# Sensor_Board.net
KiCad netlist of a schematic drawn in EAGLE
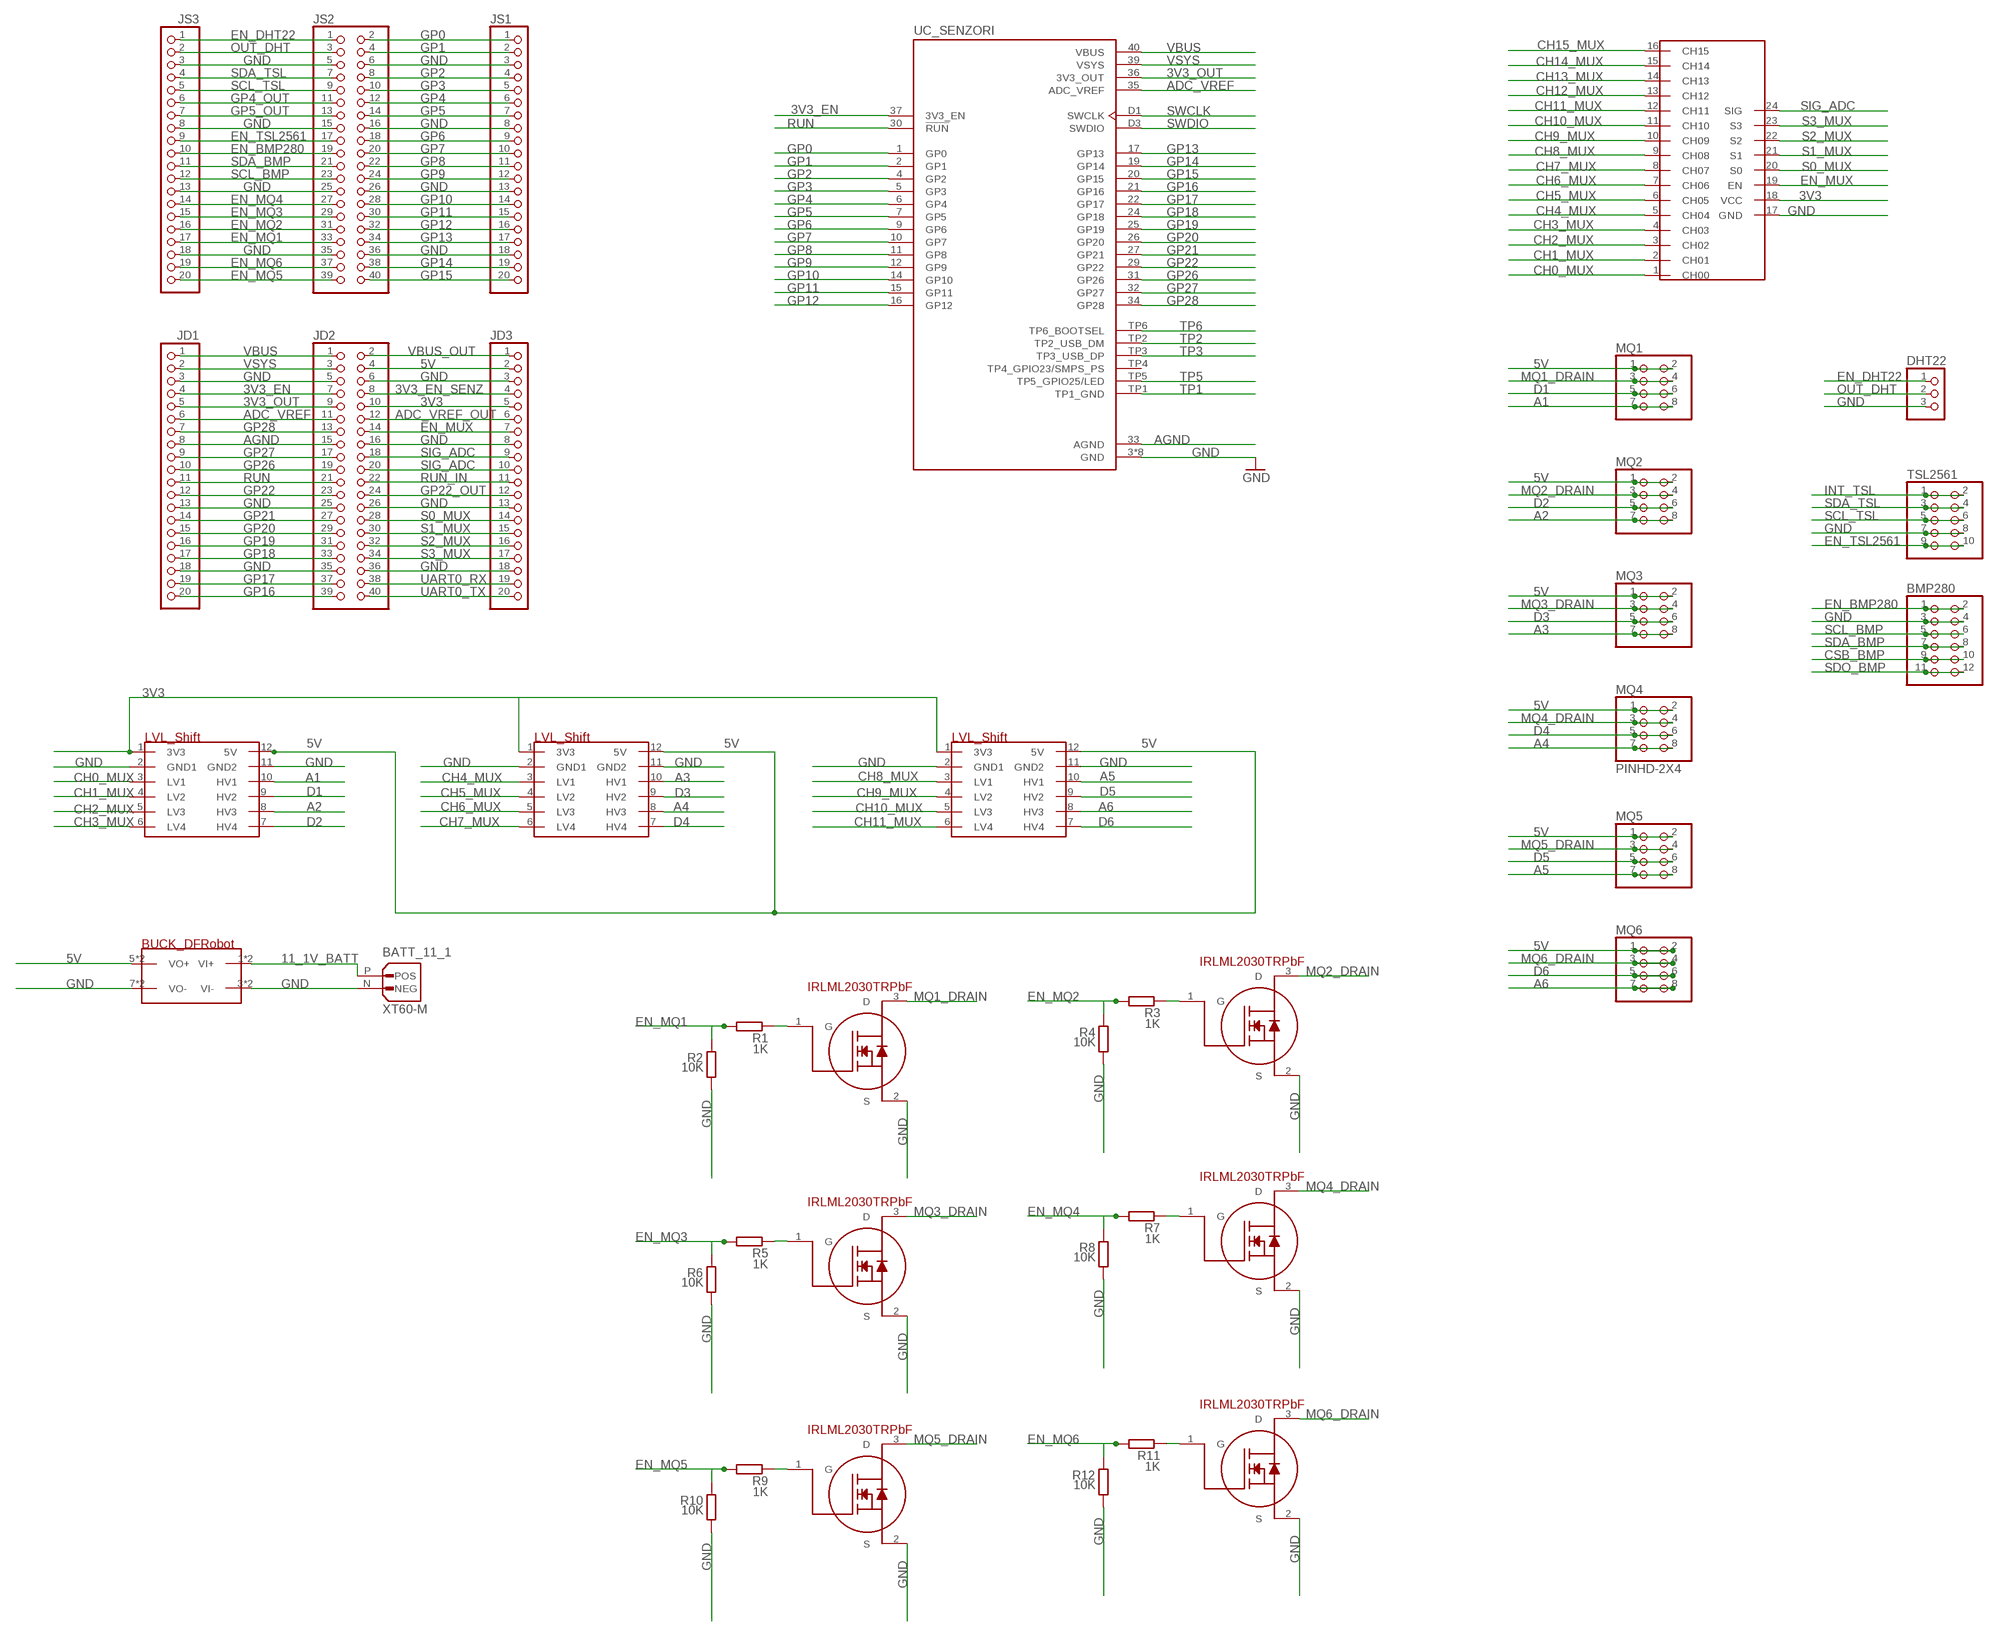
[diagram p0: schematic, sheet 1, part 1 of 2]
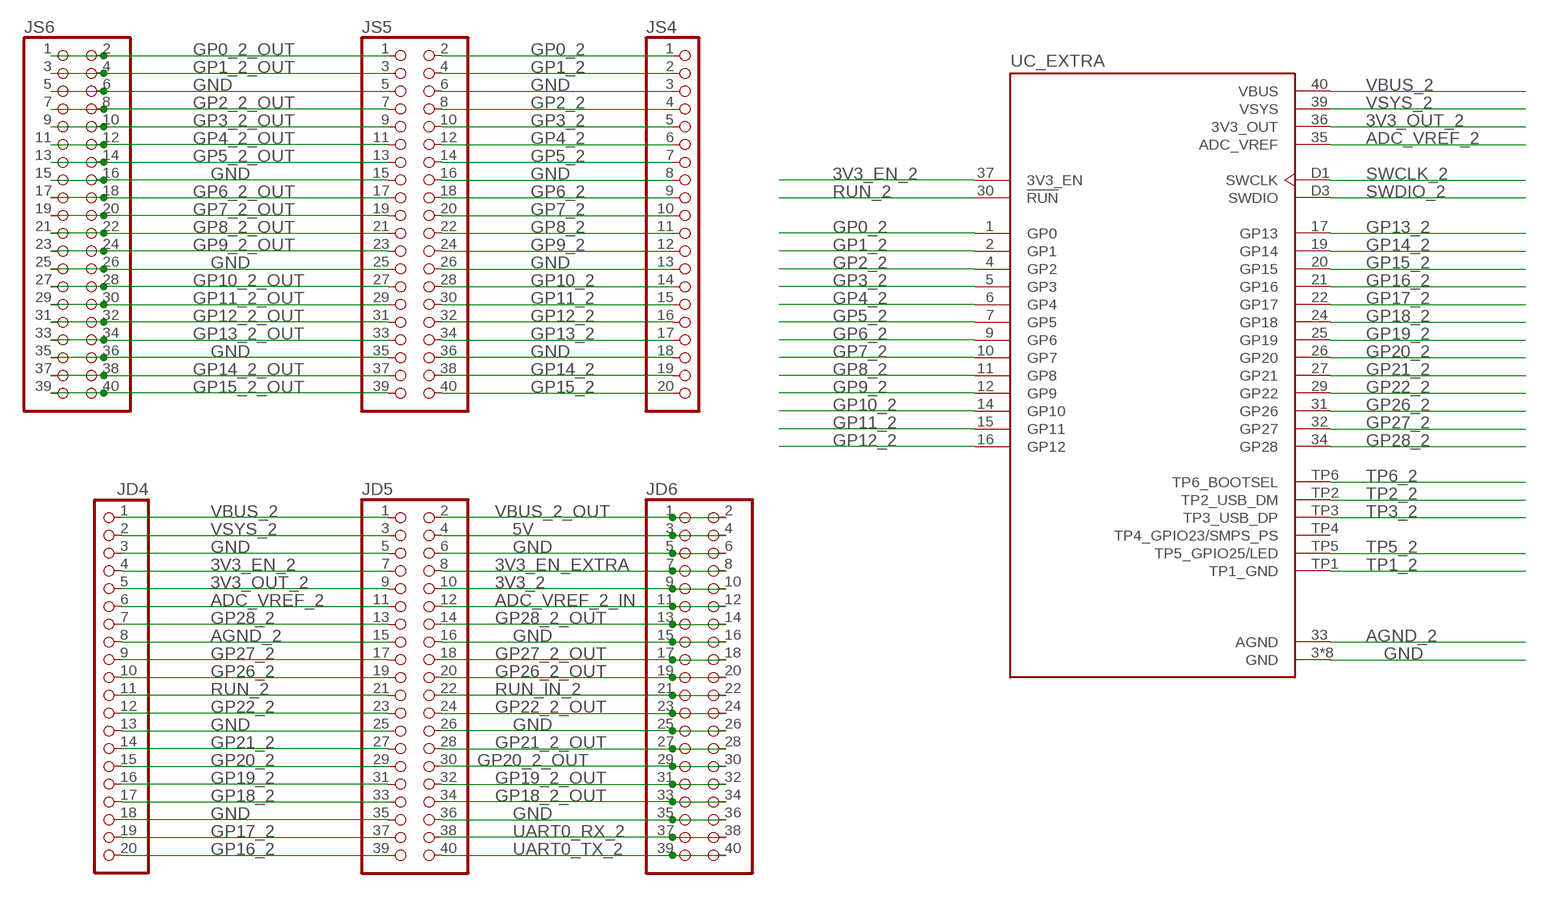
[diagram p1: schematic, sheet 1, part 2 of 2]

(export (version "E")
  (design (tool "Eeschema 10.0.6"))
  (components
    (comp (ref "BATT_11_1")
      (value "XT60-M")
      (footprint "eagle-import:AMASS_XT60-M")
      (fields (field (name "MANUFACTURER") "AMASS"))
      (libsource (lib "eagle-import") (part "XT60-M"))
    )
    (comp (ref "BMP280")
      (value "PINHD-2X6")
      (footprint "eagle-import:2X06")
      (libsource (lib "eagle-import") (part "PINHD-2X6"))
    )
    (comp (ref "DHT22")
      (value "PINHD-1X3")
      (footprint "eagle-import:1X03")
      (libsource (lib "eagle-import") (part "PINHD-1X3"))
    )
    (comp (ref "JD1")
      (value "PINHD-1X20")
      (footprint "eagle-import:1X20")
      (libsource (lib "eagle-import") (part "PINHD-1X20"))
    )
    (comp (ref "JD2")
      (value "PINHD-2X20")
      (footprint "eagle-import:2X20")
      (libsource (lib "eagle-import") (part "PINHD-2X20"))
    )
    (comp (ref "JD3")
      (value "PINHD-1X20")
      (footprint "eagle-import:1X20")
      (libsource (lib "eagle-import") (part "PINHD-1X20"))
    )
    (comp (ref "JD4")
      (value "PINHD-1X20")
      (footprint "eagle-import:1X20")
      (libsource (lib "eagle-import") (part "PINHD-1X20"))
    )
    (comp (ref "JD5")
      (value "PINHD-2X20")
      (footprint "eagle-import:2X20")
      (libsource (lib "eagle-import") (part "PINHD-2X20"))
    )
    (comp (ref "JD6")
      (value "PINHD-2X20")
      (footprint "eagle-import:2X20")
      (libsource (lib "eagle-import") (part "PINHD-2X20"))
    )
    (comp (ref "JS1")
      (value "PINHD-1X20")
      (footprint "eagle-import:1X20")
      (libsource (lib "eagle-import") (part "PINHD-1X20"))
    )
    (comp (ref "JS2")
      (value "PINHD-2X20")
      (footprint "eagle-import:2X20")
      (libsource (lib "eagle-import") (part "PINHD-2X20"))
    )
    (comp (ref "JS3")
      (value "PINHD-1X20")
      (footprint "eagle-import:1X20")
      (libsource (lib "eagle-import") (part "PINHD-1X20"))
    )
    (comp (ref "JS4")
      (value "PINHD-1X20")
      (footprint "eagle-import:1X20")
      (libsource (lib "eagle-import") (part "PINHD-1X20"))
    )
    (comp (ref "JS5")
      (value "PINHD-2X20")
      (footprint "eagle-import:2X20")
      (libsource (lib "eagle-import") (part "PINHD-2X20"))
    )
    (comp (ref "JS6")
      (value "PINHD-2X20")
      (footprint "eagle-import:2X20")
      (libsource (lib "eagle-import") (part "PINHD-2X20"))
    )
    (comp (ref "MQ1")
      (value "PINHD-2X4")
      (footprint "eagle-import:2X04")
      (libsource (lib "eagle-import") (part "PINHD-2X4"))
    )
    (comp (ref "MQ2")
      (value "PINHD-2X4")
      (footprint "eagle-import:2X04")
      (libsource (lib "eagle-import") (part "PINHD-2X4"))
    )
    (comp (ref "MQ3")
      (value "PINHD-2X4")
      (footprint "eagle-import:2X04")
      (libsource (lib "eagle-import") (part "PINHD-2X4"))
    )
    (comp (ref "MQ4")
      (value "PINHD-2X4")
      (footprint "eagle-import:2X04")
      (libsource (lib "eagle-import") (part "PINHD-2X4"))
    )
    (comp (ref "MQ5")
      (value "PINHD-2X4")
      (footprint "eagle-import:2X04")
      (libsource (lib "eagle-import") (part "PINHD-2X4"))
    )
    (comp (ref "MQ6")
      (value "PINHD-2X4")
      (footprint "eagle-import:2X04")
      (libsource (lib "eagle-import") (part "PINHD-2X4"))
    )
    (comp (ref "MUX")
      (value "CD74HC4067_MUX")
      (footprint "eagle-import:16_CH_MUX_FOOTPRINT")
      (libsource (lib "eagle-import") (part "CD74HC4067_MUX"))
    )
    (comp (ref "R1")
      (value "1K")
      (footprint "eagle-import:R0805")
      (libsource (lib "eagle-import") (part "R-EU_R0805"))
    )
    (comp (ref "R2")
      (value "10K")
      (footprint "eagle-import:R0805")
      (libsource (lib "eagle-import") (part "R-EU_R0805"))
    )
    (comp (ref "R3")
      (value "1K")
      (footprint "eagle-import:R0805")
      (libsource (lib "eagle-import") (part "R-EU_R0805"))
    )
    (comp (ref "R4")
      (value "10K")
      (footprint "eagle-import:R0805")
      (libsource (lib "eagle-import") (part "R-EU_R0805"))
    )
    (comp (ref "R5")
      (value "1K")
      (footprint "eagle-import:R0805")
      (libsource (lib "eagle-import") (part "R-EU_R0805"))
    )
    (comp (ref "R6")
      (value "10K")
      (footprint "eagle-import:R0805")
      (libsource (lib "eagle-import") (part "R-EU_R0805"))
    )
    (comp (ref "R7")
      (value "1K")
      (footprint "eagle-import:R0805")
      (libsource (lib "eagle-import") (part "R-EU_R0805"))
    )
    (comp (ref "R8")
      (value "10K")
      (footprint "eagle-import:R0805")
      (libsource (lib "eagle-import") (part "R-EU_R0805"))
    )
    (comp (ref "R9")
      (value "1K")
      (footprint "eagle-import:R0805")
      (libsource (lib "eagle-import") (part "R-EU_R0805"))
    )
    (comp (ref "R10")
      (value "10K")
      (footprint "eagle-import:R0805")
      (libsource (lib "eagle-import") (part "R-EU_R0805"))
    )
    (comp (ref "R11")
      (value "1K")
      (footprint "eagle-import:R0805")
      (libsource (lib "eagle-import") (part "R-EU_R0805"))
    )
    (comp (ref "R12")
      (value "10K")
      (footprint "eagle-import:R0805")
      (libsource (lib "eagle-import") (part "R-EU_R0805"))
    )
    (comp (ref "TSL2561")
      (value "PINHD-2X5")
      (footprint "eagle-import:2X05")
      (libsource (lib "eagle-import") (part "PINHD-2X5"))
    )
    (comp (ref "U$1")
      (value "IRLML2030TRBRBF_NMOS")
      (footprint "eagle-import:IRLML2030TRPBF_FOOTPRINT")
      (libsource (lib "eagle-import") (part "IRLML2030TRBRBF_NMOS"))
    )
    (comp (ref "U$2")
      (value "4_CH_BIDIRECTIONAL_LVL_SHIFTER")
      (footprint "eagle-import:LVL_SHIFT_FOOTPRINT")
      (libsource (lib "eagle-import") (part "4_CH_BIDIRECTIONAL_LVL_SHIFTER"))
    )
    (comp (ref "U$3")
      (value "4_CH_BIDIRECTIONAL_LVL_SHIFTER")
      (footprint "eagle-import:LVL_SHIFT_FOOTPRINT")
      (libsource (lib "eagle-import") (part "4_CH_BIDIRECTIONAL_LVL_SHIFTER"))
    )
    (comp (ref "U$4")
      (value "4_CH_BIDIRECTIONAL_LVL_SHIFTER")
      (footprint "eagle-import:LVL_SHIFT_FOOTPRINT")
      (libsource (lib "eagle-import") (part "4_CH_BIDIRECTIONAL_LVL_SHIFTER"))
    )
    (comp (ref "U$5")
      (value "DFROBOT_BUCK_CONVERTER")
      (footprint "eagle-import:DFROBOT_BUCK_FOOTPRINT")
      (libsource (lib "eagle-import") (part "DFROBOT_BUCK_CONVERTER"))
    )
    (comp (ref "U$7")
      (value "IRLML2030TRBRBF_NMOS")
      (footprint "eagle-import:IRLML2030TRPBF_FOOTPRINT")
      (libsource (lib "eagle-import") (part "IRLML2030TRBRBF_NMOS"))
    )
    (comp (ref "U$8")
      (value "IRLML2030TRBRBF_NMOS")
      (footprint "eagle-import:IRLML2030TRPBF_FOOTPRINT")
      (libsource (lib "eagle-import") (part "IRLML2030TRBRBF_NMOS"))
    )
    (comp (ref "U$9")
      (value "IRLML2030TRBRBF_NMOS")
      (footprint "eagle-import:IRLML2030TRPBF_FOOTPRINT")
      (libsource (lib "eagle-import") (part "IRLML2030TRBRBF_NMOS"))
    )
    (comp (ref "U$10")
      (value "IRLML2030TRBRBF_NMOS")
      (footprint "eagle-import:IRLML2030TRPBF_FOOTPRINT")
      (libsource (lib "eagle-import") (part "IRLML2030TRBRBF_NMOS"))
    )
    (comp (ref "U$11")
      (value "IRLML2030TRBRBF_NMOS")
      (footprint "eagle-import:IRLML2030TRPBF_FOOTPRINT")
      (libsource (lib "eagle-import") (part "IRLML2030TRBRBF_NMOS"))
    )
    (comp (ref "UC_EXTRA")
      (value "SC0915")
      (footprint "eagle-import:MODULE_SC0915")
      (fields (field (name "MF") "Raspberry Pi"))
      (libsource (lib "eagle-import") (part "SC0915"))
    )
    (comp (ref "UC_SENZORI")
      (value "SC0915")
      (footprint "eagle-import:MODULE_SC0915")
      (fields (field (name "MF") "Raspberry Pi"))
      (libsource (lib "eagle-import") (part "SC0915"))
    )
  )
  (nets
    (net (code "1") (name "/3V3") (class "Default")
      (node (ref "JD2") (pin "10") (pinfunction "10_10") (pintype "passive"))
      (node (ref "JD3") (pin "5") (pinfunction "5_5") (pintype "passive"))
      (node (ref "MUX") (pin "18") (pinfunction "VCC_18") (pintype "bidirectional"))
      (node (ref "U$2") (pin "1") (pinfunction "3V3_1") (pintype "bidirectional"))
      (node (ref "U$3") (pin "1") (pinfunction "3V3_1") (pintype "bidirectional"))
      (node (ref "U$4") (pin "1") (pinfunction "3V3_1") (pintype "bidirectional"))
    )
    (net (code "2") (name "/3V3_2") (class "Default")
      (node (ref "JD5") (pin "10") (pinfunction "10_10") (pintype "passive"))
      (node (ref "JD6") (pin "10") (pinfunction "10_10") (pintype "passive"))
      (node (ref "JD6") (pin "9") (pinfunction "9_9") (pintype "passive"))
    )
    (net (code "3") (name "/3V3_EN") (class "Default")
      (node (ref "JD1") (pin "4") (pinfunction "4_4") (pintype "passive"))
      (node (ref "JD2") (pin "7") (pinfunction "7_7") (pintype "passive"))
      (node (ref "UC_SENZORI") (pin "37") (pinfunction "3V3_EN_37") (pintype "input"))
    )
    (net (code "4") (name "/3V3_EN_2") (class "Default")
      (node (ref "JD4") (pin "4") (pinfunction "4_4") (pintype "passive"))
      (node (ref "JD5") (pin "7") (pinfunction "7_7") (pintype "passive"))
      (node (ref "UC_EXTRA") (pin "37") (pinfunction "3V3_EN_37") (pintype "input"))
    )
    (net (code "5") (name "/3V3_EN_EXTRA") (class "Default")
      (node (ref "JD5") (pin "8") (pinfunction "8_8") (pintype "passive"))
      (node (ref "JD6") (pin "7") (pinfunction "7_7") (pintype "passive"))
      (node (ref "JD6") (pin "8") (pinfunction "8_8") (pintype "passive"))
    )
    (net (code "6") (name "/3V3_EN_SENZ") (class "Default")
      (node (ref "JD2") (pin "8") (pinfunction "8_8") (pintype "passive"))
      (node (ref "JD3") (pin "4") (pinfunction "4_4") (pintype "passive"))
    )
    (net (code "7") (name "/3V3_OUT") (class "Default")
      (node (ref "JD1") (pin "5") (pinfunction "5_5") (pintype "passive"))
      (node (ref "JD2") (pin "9") (pinfunction "9_9") (pintype "passive"))
      (node (ref "UC_SENZORI") (pin "36") (pinfunction "3V3_OUT_36") (pintype "power_in"))
    )
    (net (code "8") (name "/3V3_OUT_2") (class "Default")
      (node (ref "JD4") (pin "5") (pinfunction "5_5") (pintype "passive"))
      (node (ref "JD5") (pin "9") (pinfunction "9_9") (pintype "passive"))
      (node (ref "UC_EXTRA") (pin "36") (pinfunction "3V3_OUT_36") (pintype "power_in"))
    )
    (net (code "9") (name "/5V") (class "Default")
      (node (ref "JD2") (pin "4") (pinfunction "4_4") (pintype "passive"))
      (node (ref "JD3") (pin "2") (pinfunction "2_2") (pintype "passive"))
      (node (ref "JD5") (pin "4") (pinfunction "4_4") (pintype "passive"))
      (node (ref "JD6") (pin "3") (pinfunction "3_3") (pintype "passive"))
      (node (ref "JD6") (pin "4") (pinfunction "4_4") (pintype "passive"))
      (node (ref "MQ1") (pin "1") (pinfunction "1_1") (pintype "passive"))
      (node (ref "MQ1") (pin "2") (pinfunction "2_2") (pintype "passive"))
      (node (ref "MQ2") (pin "1") (pinfunction "1_1") (pintype "passive"))
      (node (ref "MQ2") (pin "2") (pinfunction "2_2") (pintype "passive"))
      (node (ref "MQ3") (pin "1") (pinfunction "1_1") (pintype "passive"))
      (node (ref "MQ3") (pin "2") (pinfunction "2_2") (pintype "passive"))
      (node (ref "MQ4") (pin "1") (pinfunction "1_1") (pintype "passive"))
      (node (ref "MQ4") (pin "2") (pinfunction "2_2") (pintype "passive"))
      (node (ref "MQ5") (pin "1") (pinfunction "1_1") (pintype "passive"))
      (node (ref "MQ5") (pin "2") (pinfunction "2_2") (pintype "passive"))
      (node (ref "MQ6") (pin "1") (pinfunction "1_1") (pintype "passive"))
      (node (ref "MQ6") (pin "2") (pinfunction "2_2") (pintype "passive"))
      (node (ref "U$2") (pin "12") (pinfunction "5V_12") (pintype "bidirectional"))
      (node (ref "U$3") (pin "12") (pinfunction "5V_12") (pintype "bidirectional"))
      (node (ref "U$4") (pin "12") (pinfunction "5V_12") (pintype "bidirectional"))
      (node (ref "U$5") (pin "5") (pinfunction "VO+_5") (pintype "output"))
      (node (ref "U$5") (pin "6") (pinfunction "VO+_6") (pintype "output"))
    )
    (net (code "10") (name "/11_1V_BATT") (class "Default")
      (node (ref "BATT_11_1") (pin "P") (pinfunction "POS_P") (pintype "passive"))
      (node (ref "U$5") (pin "1") (pinfunction "VI+_1") (pintype "input"))
      (node (ref "U$5") (pin "2") (pinfunction "VI+_2") (pintype "input"))
    )
    (net (code "11") (name "/A1") (class "Default")
      (node (ref "MQ1") (pin "7") (pinfunction "7_7") (pintype "passive"))
      (node (ref "MQ1") (pin "8") (pinfunction "8_8") (pintype "passive"))
      (node (ref "U$2") (pin "10") (pinfunction "HV1_10") (pintype "bidirectional"))
    )
    (net (code "12") (name "/A2") (class "Default")
      (node (ref "MQ2") (pin "7") (pinfunction "7_7") (pintype "passive"))
      (node (ref "MQ2") (pin "8") (pinfunction "8_8") (pintype "passive"))
      (node (ref "U$2") (pin "8") (pinfunction "HV3_8") (pintype "bidirectional"))
    )
    (net (code "13") (name "/A3") (class "Default")
      (node (ref "MQ3") (pin "7") (pinfunction "7_7") (pintype "passive"))
      (node (ref "MQ3") (pin "8") (pinfunction "8_8") (pintype "passive"))
      (node (ref "U$3") (pin "10") (pinfunction "HV1_10") (pintype "bidirectional"))
    )
    (net (code "14") (name "/A4") (class "Default")
      (node (ref "MQ4") (pin "7") (pinfunction "7_7") (pintype "passive"))
      (node (ref "MQ4") (pin "8") (pinfunction "8_8") (pintype "passive"))
      (node (ref "U$3") (pin "8") (pinfunction "HV3_8") (pintype "bidirectional"))
    )
    (net (code "15") (name "/A5") (class "Default")
      (node (ref "MQ5") (pin "7") (pinfunction "7_7") (pintype "passive"))
      (node (ref "MQ5") (pin "8") (pinfunction "8_8") (pintype "passive"))
      (node (ref "U$4") (pin "10") (pinfunction "HV1_10") (pintype "bidirectional"))
    )
    (net (code "16") (name "/A6") (class "Default")
      (node (ref "MQ6") (pin "7") (pinfunction "7_7") (pintype "passive"))
      (node (ref "MQ6") (pin "8") (pinfunction "8_8") (pintype "passive"))
      (node (ref "U$4") (pin "8") (pinfunction "HV3_8") (pintype "bidirectional"))
    )
    (net (code "17") (name "/ADC_VREF") (class "Default")
      (node (ref "JD1") (pin "6") (pinfunction "6_6") (pintype "passive"))
      (node (ref "JD2") (pin "11") (pinfunction "11_11") (pintype "passive"))
      (node (ref "UC_SENZORI") (pin "35") (pinfunction "ADC_VREF_35") (pintype "power_in"))
    )
    (net (code "18") (name "/ADC_VREF_2") (class "Default")
      (node (ref "JD4") (pin "6") (pinfunction "6_6") (pintype "passive"))
      (node (ref "JD5") (pin "11") (pinfunction "11_11") (pintype "passive"))
      (node (ref "UC_EXTRA") (pin "35") (pinfunction "ADC_VREF_35") (pintype "power_in"))
    )
    (net (code "19") (name "/ADC_VREF_2_IN") (class "Default")
      (node (ref "JD5") (pin "12") (pinfunction "12_12") (pintype "passive"))
      (node (ref "JD6") (pin "11") (pinfunction "11_11") (pintype "passive"))
      (node (ref "JD6") (pin "12") (pinfunction "12_12") (pintype "passive"))
    )
    (net (code "20") (name "/ADC_VREF_OUT") (class "Default")
      (node (ref "JD2") (pin "12") (pinfunction "12_12") (pintype "passive"))
      (node (ref "JD3") (pin "6") (pinfunction "6_6") (pintype "passive"))
    )
    (net (code "21") (name "/AGND") (class "Default")
      (node (ref "JD1") (pin "8") (pinfunction "8_8") (pintype "passive"))
      (node (ref "JD2") (pin "15") (pinfunction "15_15") (pintype "passive"))
      (node (ref "UC_SENZORI") (pin "33") (pinfunction "AGND_33") (pintype "power_in"))
    )
    (net (code "22") (name "/AGND_2") (class "Default")
      (node (ref "JD4") (pin "8") (pinfunction "8_8") (pintype "passive"))
      (node (ref "JD5") (pin "15") (pinfunction "15_15") (pintype "passive"))
      (node (ref "UC_EXTRA") (pin "33") (pinfunction "AGND_33") (pintype "power_in"))
    )
    (net (code "23") (name "/CH0_MUX") (class "Default")
      (node (ref "MUX") (pin "1") (pinfunction "CH00_1") (pintype "bidirectional"))
      (node (ref "U$2") (pin "3") (pinfunction "LV1_3") (pintype "bidirectional"))
    )
    (net (code "24") (name "/CH1_MUX") (class "Default")
      (node (ref "MUX") (pin "2") (pinfunction "CH01_2") (pintype "bidirectional"))
      (node (ref "U$2") (pin "4") (pinfunction "LV2_4") (pintype "bidirectional"))
    )
    (net (code "25") (name "/CH2_MUX") (class "Default")
      (node (ref "MUX") (pin "3") (pinfunction "CH02_3") (pintype "bidirectional"))
      (node (ref "U$2") (pin "5") (pinfunction "LV3_5") (pintype "bidirectional"))
    )
    (net (code "26") (name "/CH3_MUX") (class "Default")
      (node (ref "MUX") (pin "4") (pinfunction "CH03_4") (pintype "bidirectional"))
      (node (ref "U$2") (pin "6") (pinfunction "LV4_6") (pintype "bidirectional"))
    )
    (net (code "27") (name "/CH4_MUX") (class "Default")
      (node (ref "MUX") (pin "5") (pinfunction "CH04_5") (pintype "bidirectional"))
      (node (ref "U$3") (pin "3") (pinfunction "LV1_3") (pintype "bidirectional"))
    )
    (net (code "28") (name "/CH5_MUX") (class "Default")
      (node (ref "MUX") (pin "6") (pinfunction "CH05_6") (pintype "bidirectional"))
      (node (ref "U$3") (pin "4") (pinfunction "LV2_4") (pintype "bidirectional"))
    )
    (net (code "29") (name "/CH6_MUX") (class "Default")
      (node (ref "MUX") (pin "7") (pinfunction "CH06_7") (pintype "bidirectional"))
      (node (ref "U$3") (pin "5") (pinfunction "LV3_5") (pintype "bidirectional"))
    )
    (net (code "30") (name "/CH7_MUX") (class "Default")
      (node (ref "MUX") (pin "8") (pinfunction "CH07_8") (pintype "bidirectional"))
      (node (ref "U$3") (pin "6") (pinfunction "LV4_6") (pintype "bidirectional"))
    )
    (net (code "31") (name "/CH8_MUX") (class "Default")
      (node (ref "MUX") (pin "9") (pinfunction "CH08_9") (pintype "bidirectional"))
      (node (ref "U$4") (pin "3") (pinfunction "LV1_3") (pintype "bidirectional"))
    )
    (net (code "32") (name "/CH9_MUX") (class "Default")
      (node (ref "MUX") (pin "10") (pinfunction "CH09_10") (pintype "bidirectional"))
      (node (ref "U$4") (pin "4") (pinfunction "LV2_4") (pintype "bidirectional"))
    )
    (net (code "33") (name "/CH10_MUX") (class "Default")
      (node (ref "MUX") (pin "11") (pinfunction "CH10_11") (pintype "bidirectional"))
      (node (ref "U$4") (pin "5") (pinfunction "LV3_5") (pintype "bidirectional"))
    )
    (net (code "34") (name "/CH11_MUX") (class "Default")
      (node (ref "MUX") (pin "12") (pinfunction "CH11_12") (pintype "bidirectional"))
      (node (ref "U$4") (pin "6") (pinfunction "LV4_6") (pintype "bidirectional"))
    )
    (net (code "35") (name "/CH12_MUX") (class "Default")
      (node (ref "MUX") (pin "13") (pinfunction "CH12_13") (pintype "bidirectional"))
    )
    (net (code "36") (name "/CH13_MUX") (class "Default")
      (node (ref "MUX") (pin "14") (pinfunction "CH13_14") (pintype "bidirectional"))
    )
    (net (code "37") (name "/CH14_MUX") (class "Default")
      (node (ref "MUX") (pin "15") (pinfunction "CH14_15") (pintype "bidirectional"))
    )
    (net (code "38") (name "/CH15_MUX") (class "Default")
      (node (ref "MUX") (pin "16") (pinfunction "CH15_16") (pintype "bidirectional"))
    )
    (net (code "39") (name "/CSB_BMP") (class "Default")
      (node (ref "BMP280") (pin "10") (pinfunction "10_10") (pintype "passive"))
      (node (ref "BMP280") (pin "9") (pinfunction "9_9") (pintype "passive"))
    )
    (net (code "40") (name "/D1") (class "Default")
      (node (ref "MQ1") (pin "5") (pinfunction "5_5") (pintype "passive"))
      (node (ref "MQ1") (pin "6") (pinfunction "6_6") (pintype "passive"))
      (node (ref "U$2") (pin "9") (pinfunction "HV2_9") (pintype "bidirectional"))
    )
    (net (code "41") (name "/D2") (class "Default")
      (node (ref "MQ2") (pin "5") (pinfunction "5_5") (pintype "passive"))
      (node (ref "MQ2") (pin "6") (pinfunction "6_6") (pintype "passive"))
      (node (ref "U$2") (pin "7") (pinfunction "HV4_7") (pintype "bidirectional"))
    )
    (net (code "42") (name "/D3") (class "Default")
      (node (ref "MQ3") (pin "5") (pinfunction "5_5") (pintype "passive"))
      (node (ref "MQ3") (pin "6") (pinfunction "6_6") (pintype "passive"))
      (node (ref "U$3") (pin "9") (pinfunction "HV2_9") (pintype "bidirectional"))
    )
    (net (code "43") (name "/D4") (class "Default")
      (node (ref "MQ4") (pin "5") (pinfunction "5_5") (pintype "passive"))
      (node (ref "MQ4") (pin "6") (pinfunction "6_6") (pintype "passive"))
      (node (ref "U$3") (pin "7") (pinfunction "HV4_7") (pintype "bidirectional"))
    )
    (net (code "44") (name "/D5") (class "Default")
      (node (ref "MQ5") (pin "5") (pinfunction "5_5") (pintype "passive"))
      (node (ref "MQ5") (pin "6") (pinfunction "6_6") (pintype "passive"))
      (node (ref "U$4") (pin "9") (pinfunction "HV2_9") (pintype "bidirectional"))
    )
    (net (code "45") (name "/D6") (class "Default")
      (node (ref "MQ6") (pin "5") (pinfunction "5_5") (pintype "passive"))
      (node (ref "MQ6") (pin "6") (pinfunction "6_6") (pintype "passive"))
      (node (ref "U$4") (pin "7") (pinfunction "HV4_7") (pintype "bidirectional"))
    )
    (net (code "46") (name "/EN_BMP280") (class "Default")
      (node (ref "BMP280") (pin "1") (pinfunction "1_1") (pintype "passive"))
      (node (ref "BMP280") (pin "2") (pinfunction "2_2") (pintype "passive"))
      (node (ref "JS2") (pin "19") (pinfunction "19_19") (pintype "passive"))
      (node (ref "JS3") (pin "10") (pinfunction "10_10") (pintype "passive"))
    )
    (net (code "47") (name "/EN_DHT22") (class "Default")
      (node (ref "DHT22") (pin "1") (pinfunction "1_1") (pintype "passive"))
      (node (ref "JS2") (pin "1") (pinfunction "1_1") (pintype "passive"))
      (node (ref "JS3") (pin "1") (pinfunction "1_1") (pintype "passive"))
    )
    (net (code "48") (name "/EN_MQ1") (class "Default")
      (node (ref "JS2") (pin "33") (pinfunction "33_33") (pintype "passive"))
      (node (ref "JS3") (pin "17") (pinfunction "17_17") (pintype "passive"))
      (node (ref "R1") (pin "2") (pinfunction "2_2") (pintype "passive"))
      (node (ref "R2") (pin "2") (pinfunction "2_2") (pintype "passive"))
    )
    (net (code "49") (name "/EN_MQ2") (class "Default")
      (node (ref "JS2") (pin "31") (pinfunction "31_31") (pintype "passive"))
      (node (ref "JS3") (pin "16") (pinfunction "16_16") (pintype "passive"))
      (node (ref "R3") (pin "2") (pinfunction "2_2") (pintype "passive"))
      (node (ref "R4") (pin "2") (pinfunction "2_2") (pintype "passive"))
    )
    (net (code "50") (name "/EN_MQ3") (class "Default")
      (node (ref "JS2") (pin "29") (pinfunction "29_29") (pintype "passive"))
      (node (ref "JS3") (pin "15") (pinfunction "15_15") (pintype "passive"))
      (node (ref "R5") (pin "2") (pinfunction "2_2") (pintype "passive"))
      (node (ref "R6") (pin "2") (pinfunction "2_2") (pintype "passive"))
    )
    (net (code "51") (name "/EN_MQ4") (class "Default")
      (node (ref "JS2") (pin "27") (pinfunction "27_27") (pintype "passive"))
      (node (ref "JS3") (pin "14") (pinfunction "14_14") (pintype "passive"))
      (node (ref "R7") (pin "2") (pinfunction "2_2") (pintype "passive"))
      (node (ref "R8") (pin "2") (pinfunction "2_2") (pintype "passive"))
    )
    (net (code "52") (name "/EN_MQ5") (class "Default")
      (node (ref "JS2") (pin "39") (pinfunction "39_39") (pintype "passive"))
      (node (ref "JS3") (pin "20") (pinfunction "20_20") (pintype "passive"))
      (node (ref "R10") (pin "2") (pinfunction "2_2") (pintype "passive"))
      (node (ref "R9") (pin "2") (pinfunction "2_2") (pintype "passive"))
    )
    (net (code "53") (name "/EN_MQ6") (class "Default")
      (node (ref "JS2") (pin "37") (pinfunction "37_37") (pintype "passive"))
      (node (ref "JS3") (pin "19") (pinfunction "19_19") (pintype "passive"))
      (node (ref "R11") (pin "2") (pinfunction "2_2") (pintype "passive"))
      (node (ref "R12") (pin "2") (pinfunction "2_2") (pintype "passive"))
    )
    (net (code "54") (name "/EN_MUX") (class "Default")
      (node (ref "JD2") (pin "14") (pinfunction "14_14") (pintype "passive"))
      (node (ref "JD3") (pin "7") (pinfunction "7_7") (pintype "passive"))
      (node (ref "MUX") (pin "19") (pinfunction "EN_19") (pintype "bidirectional"))
    )
    (net (code "55") (name "/EN_TSL2561") (class "Default")
      (node (ref "JS2") (pin "17") (pinfunction "17_17") (pintype "passive"))
      (node (ref "JS3") (pin "9") (pinfunction "9_9") (pintype "passive"))
      (node (ref "TSL2561") (pin "10") (pinfunction "10_10") (pintype "passive"))
      (node (ref "TSL2561") (pin "9") (pinfunction "9_9") (pintype "passive"))
    )
    (net (code "56") (name "/GP0") (class "Default")
      (node (ref "JS1") (pin "1") (pinfunction "1_1") (pintype "passive"))
      (node (ref "JS2") (pin "2") (pinfunction "2_2") (pintype "passive"))
      (node (ref "UC_SENZORI") (pin "1") (pinfunction "GP0_1") (pintype "bidirectional"))
    )
    (net (code "57") (name "/GP0_2") (class "Default")
      (node (ref "JS4") (pin "1") (pinfunction "1_1") (pintype "passive"))
      (node (ref "JS5") (pin "2") (pinfunction "2_2") (pintype "passive"))
      (node (ref "UC_EXTRA") (pin "1") (pinfunction "GP0_1") (pintype "bidirectional"))
    )
    (net (code "58") (name "/GP0_2_OUT") (class "Default")
      (node (ref "JS5") (pin "1") (pinfunction "1_1") (pintype "passive"))
      (node (ref "JS6") (pin "1") (pinfunction "1_1") (pintype "passive"))
      (node (ref "JS6") (pin "2") (pinfunction "2_2") (pintype "passive"))
    )
    (net (code "59") (name "/GP1") (class "Default")
      (node (ref "JS1") (pin "2") (pinfunction "2_2") (pintype "passive"))
      (node (ref "JS2") (pin "4") (pinfunction "4_4") (pintype "passive"))
      (node (ref "UC_SENZORI") (pin "2") (pinfunction "GP1_2") (pintype "bidirectional"))
    )
    (net (code "60") (name "/GP1_2") (class "Default")
      (node (ref "JS4") (pin "2") (pinfunction "2_2") (pintype "passive"))
      (node (ref "JS5") (pin "4") (pinfunction "4_4") (pintype "passive"))
      (node (ref "UC_EXTRA") (pin "2") (pinfunction "GP1_2") (pintype "bidirectional"))
    )
    (net (code "61") (name "/GP1_2_OUT") (class "Default")
      (node (ref "JS5") (pin "3") (pinfunction "3_3") (pintype "passive"))
      (node (ref "JS6") (pin "3") (pinfunction "3_3") (pintype "passive"))
      (node (ref "JS6") (pin "4") (pinfunction "4_4") (pintype "passive"))
    )
    (net (code "62") (name "/GP2") (class "Default")
      (node (ref "JS1") (pin "4") (pinfunction "4_4") (pintype "passive"))
      (node (ref "JS2") (pin "8") (pinfunction "8_8") (pintype "passive"))
      (node (ref "UC_SENZORI") (pin "4") (pinfunction "GP2_4") (pintype "bidirectional"))
    )
    (net (code "63") (name "/GP2_2") (class "Default")
      (node (ref "JS4") (pin "4") (pinfunction "4_4") (pintype "passive"))
      (node (ref "JS5") (pin "8") (pinfunction "8_8") (pintype "passive"))
      (node (ref "UC_EXTRA") (pin "4") (pinfunction "GP2_4") (pintype "bidirectional"))
    )
    (net (code "64") (name "/GP2_2_OUT") (class "Default")
      (node (ref "JS5") (pin "7") (pinfunction "7_7") (pintype "passive"))
      (node (ref "JS6") (pin "7") (pinfunction "7_7") (pintype "passive"))
      (node (ref "JS6") (pin "8") (pinfunction "8_8") (pintype "passive"))
    )
    (net (code "65") (name "/GP3") (class "Default")
      (node (ref "JS1") (pin "5") (pinfunction "5_5") (pintype "passive"))
      (node (ref "JS2") (pin "10") (pinfunction "10_10") (pintype "passive"))
      (node (ref "UC_SENZORI") (pin "5") (pinfunction "GP3_5") (pintype "bidirectional"))
    )
    (net (code "66") (name "/GP3_2") (class "Default")
      (node (ref "JS4") (pin "5") (pinfunction "5_5") (pintype "passive"))
      (node (ref "JS5") (pin "10") (pinfunction "10_10") (pintype "passive"))
      (node (ref "UC_EXTRA") (pin "5") (pinfunction "GP3_5") (pintype "bidirectional"))
    )
    (net (code "67") (name "/GP3_2_OUT") (class "Default")
      (node (ref "JS5") (pin "9") (pinfunction "9_9") (pintype "passive"))
      (node (ref "JS6") (pin "10") (pinfunction "10_10") (pintype "passive"))
      (node (ref "JS6") (pin "9") (pinfunction "9_9") (pintype "passive"))
    )
    (net (code "68") (name "/GP4") (class "Default")
      (node (ref "JS1") (pin "6") (pinfunction "6_6") (pintype "passive"))
      (node (ref "JS2") (pin "12") (pinfunction "12_12") (pintype "passive"))
      (node (ref "UC_SENZORI") (pin "6") (pinfunction "GP4_6") (pintype "bidirectional"))
    )
    (net (code "69") (name "/GP4_2") (class "Default")
      (node (ref "JS4") (pin "6") (pinfunction "6_6") (pintype "passive"))
      (node (ref "JS5") (pin "12") (pinfunction "12_12") (pintype "passive"))
      (node (ref "UC_EXTRA") (pin "6") (pinfunction "GP4_6") (pintype "bidirectional"))
    )
    (net (code "70") (name "/GP4_2_OUT") (class "Default")
      (node (ref "JS5") (pin "11") (pinfunction "11_11") (pintype "passive"))
      (node (ref "JS6") (pin "11") (pinfunction "11_11") (pintype "passive"))
      (node (ref "JS6") (pin "12") (pinfunction "12_12") (pintype "passive"))
    )
    (net (code "71") (name "/GP4_OUT") (class "Default")
      (node (ref "JS2") (pin "11") (pinfunction "11_11") (pintype "passive"))
      (node (ref "JS3") (pin "6") (pinfunction "6_6") (pintype "passive"))
    )
    (net (code "72") (name "/GP5") (class "Default")
      (node (ref "JS1") (pin "7") (pinfunction "7_7") (pintype "passive"))
      (node (ref "JS2") (pin "14") (pinfunction "14_14") (pintype "passive"))
      (node (ref "UC_SENZORI") (pin "7") (pinfunction "GP5_7") (pintype "bidirectional"))
    )
    (net (code "73") (name "/GP5_2") (class "Default")
      (node (ref "JS4") (pin "7") (pinfunction "7_7") (pintype "passive"))
      (node (ref "JS5") (pin "14") (pinfunction "14_14") (pintype "passive"))
      (node (ref "UC_EXTRA") (pin "7") (pinfunction "GP5_7") (pintype "bidirectional"))
    )
    (net (code "74") (name "/GP5_2_OUT") (class "Default")
      (node (ref "JS5") (pin "13") (pinfunction "13_13") (pintype "passive"))
      (node (ref "JS6") (pin "13") (pinfunction "13_13") (pintype "passive"))
      (node (ref "JS6") (pin "14") (pinfunction "14_14") (pintype "passive"))
    )
    (net (code "75") (name "/GP5_OUT") (class "Default")
      (node (ref "JS2") (pin "13") (pinfunction "13_13") (pintype "passive"))
      (node (ref "JS3") (pin "7") (pinfunction "7_7") (pintype "passive"))
    )
    (net (code "76") (name "/GP6") (class "Default")
      (node (ref "JS1") (pin "9") (pinfunction "9_9") (pintype "passive"))
      (node (ref "JS2") (pin "18") (pinfunction "18_18") (pintype "passive"))
      (node (ref "UC_SENZORI") (pin "9") (pinfunction "GP6_9") (pintype "bidirectional"))
    )
    (net (code "77") (name "/GP6_2") (class "Default")
      (node (ref "JS4") (pin "9") (pinfunction "9_9") (pintype "passive"))
      (node (ref "JS5") (pin "18") (pinfunction "18_18") (pintype "passive"))
      (node (ref "UC_EXTRA") (pin "9") (pinfunction "GP6_9") (pintype "bidirectional"))
    )
    (net (code "78") (name "/GP6_2_OUT") (class "Default")
      (node (ref "JS5") (pin "17") (pinfunction "17_17") (pintype "passive"))
      (node (ref "JS6") (pin "17") (pinfunction "17_17") (pintype "passive"))
      (node (ref "JS6") (pin "18") (pinfunction "18_18") (pintype "passive"))
    )
    (net (code "79") (name "/GP7") (class "Default")
      (node (ref "JS1") (pin "10") (pinfunction "10_10") (pintype "passive"))
      (node (ref "JS2") (pin "20") (pinfunction "20_20") (pintype "passive"))
      (node (ref "UC_SENZORI") (pin "10") (pinfunction "GP7_10") (pintype "bidirectional"))
    )
    (net (code "80") (name "/GP7_2") (class "Default")
      (node (ref "JS4") (pin "10") (pinfunction "10_10") (pintype "passive"))
      (node (ref "JS5") (pin "20") (pinfunction "20_20") (pintype "passive"))
      (node (ref "UC_EXTRA") (pin "10") (pinfunction "GP7_10") (pintype "bidirectional"))
    )
    (net (code "81") (name "/GP7_2_OUT") (class "Default")
      (node (ref "JS5") (pin "19") (pinfunction "19_19") (pintype "passive"))
      (node (ref "JS6") (pin "19") (pinfunction "19_19") (pintype "passive"))
      (node (ref "JS6") (pin "20") (pinfunction "20_20") (pintype "passive"))
    )
    (net (code "82") (name "/GP8") (class "Default")
      (node (ref "JS1") (pin "11") (pinfunction "11_11") (pintype "passive"))
      (node (ref "JS2") (pin "22") (pinfunction "22_22") (pintype "passive"))
      (node (ref "UC_SENZORI") (pin "11") (pinfunction "GP8_11") (pintype "bidirectional"))
    )
    (net (code "83") (name "/GP8_2") (class "Default")
      (node (ref "JS4") (pin "11") (pinfunction "11_11") (pintype "passive"))
      (node (ref "JS5") (pin "22") (pinfunction "22_22") (pintype "passive"))
      (node (ref "UC_EXTRA") (pin "11") (pinfunction "GP8_11") (pintype "bidirectional"))
    )
    (net (code "84") (name "/GP8_2_OUT") (class "Default")
      (node (ref "JS5") (pin "21") (pinfunction "21_21") (pintype "passive"))
      (node (ref "JS6") (pin "21") (pinfunction "21_21") (pintype "passive"))
      (node (ref "JS6") (pin "22") (pinfunction "22_22") (pintype "passive"))
    )
    (net (code "85") (name "/GP9") (class "Default")
      (node (ref "JS1") (pin "12") (pinfunction "12_12") (pintype "passive"))
      (node (ref "JS2") (pin "24") (pinfunction "24_24") (pintype "passive"))
      (node (ref "UC_SENZORI") (pin "12") (pinfunction "GP9_12") (pintype "bidirectional"))
    )
    (net (code "86") (name "/GP9_2") (class "Default")
      (node (ref "JS4") (pin "12") (pinfunction "12_12") (pintype "passive"))
      (node (ref "JS5") (pin "24") (pinfunction "24_24") (pintype "passive"))
      (node (ref "UC_EXTRA") (pin "12") (pinfunction "GP9_12") (pintype "bidirectional"))
    )
    (net (code "87") (name "/GP9_2_OUT") (class "Default")
      (node (ref "JS5") (pin "23") (pinfunction "23_23") (pintype "passive"))
      (node (ref "JS6") (pin "23") (pinfunction "23_23") (pintype "passive"))
      (node (ref "JS6") (pin "24") (pinfunction "24_24") (pintype "passive"))
    )
    (net (code "88") (name "/GP10") (class "Default")
      (node (ref "JS1") (pin "14") (pinfunction "14_14") (pintype "passive"))
      (node (ref "JS2") (pin "28") (pinfunction "28_28") (pintype "passive"))
      (node (ref "UC_SENZORI") (pin "14") (pinfunction "GP10_14") (pintype "bidirectional"))
    )
    (net (code "89") (name "/GP10_2") (class "Default")
      (node (ref "JS4") (pin "14") (pinfunction "14_14") (pintype "passive"))
      (node (ref "JS5") (pin "28") (pinfunction "28_28") (pintype "passive"))
      (node (ref "UC_EXTRA") (pin "14") (pinfunction "GP10_14") (pintype "bidirectional"))
    )
    (net (code "90") (name "/GP10_2_OUT") (class "Default")
      (node (ref "JS5") (pin "27") (pinfunction "27_27") (pintype "passive"))
      (node (ref "JS6") (pin "27") (pinfunction "27_27") (pintype "passive"))
      (node (ref "JS6") (pin "28") (pinfunction "28_28") (pintype "passive"))
    )
    (net (code "91") (name "/GP11") (class "Default")
      (node (ref "JS1") (pin "15") (pinfunction "15_15") (pintype "passive"))
      (node (ref "JS2") (pin "30") (pinfunction "30_30") (pintype "passive"))
      (node (ref "UC_SENZORI") (pin "15") (pinfunction "GP11_15") (pintype "bidirectional"))
    )
    (net (code "92") (name "/GP11_2") (class "Default")
      (node (ref "JS4") (pin "15") (pinfunction "15_15") (pintype "passive"))
      (node (ref "JS5") (pin "30") (pinfunction "30_30") (pintype "passive"))
      (node (ref "UC_EXTRA") (pin "15") (pinfunction "GP11_15") (pintype "bidirectional"))
    )
    (net (code "93") (name "/GP11_2_OUT") (class "Default")
      (node (ref "JS5") (pin "29") (pinfunction "29_29") (pintype "passive"))
      (node (ref "JS6") (pin "29") (pinfunction "29_29") (pintype "passive"))
      (node (ref "JS6") (pin "30") (pinfunction "30_30") (pintype "passive"))
    )
    (net (code "94") (name "/GP12") (class "Default")
      (node (ref "JS1") (pin "16") (pinfunction "16_16") (pintype "passive"))
      (node (ref "JS2") (pin "32") (pinfunction "32_32") (pintype "passive"))
      (node (ref "UC_SENZORI") (pin "16") (pinfunction "GP12_16") (pintype "bidirectional"))
    )
    (net (code "95") (name "/GP12_2") (class "Default")
      (node (ref "JS4") (pin "16") (pinfunction "16_16") (pintype "passive"))
      (node (ref "JS5") (pin "32") (pinfunction "32_32") (pintype "passive"))
      (node (ref "UC_EXTRA") (pin "16") (pinfunction "GP12_16") (pintype "bidirectional"))
    )
    (net (code "96") (name "/GP12_2_OUT") (class "Default")
      (node (ref "JS5") (pin "31") (pinfunction "31_31") (pintype "passive"))
      (node (ref "JS6") (pin "31") (pinfunction "31_31") (pintype "passive"))
      (node (ref "JS6") (pin "32") (pinfunction "32_32") (pintype "passive"))
    )
    (net (code "97") (name "/GP13") (class "Default")
      (node (ref "JS1") (pin "17") (pinfunction "17_17") (pintype "passive"))
      (node (ref "JS2") (pin "34") (pinfunction "34_34") (pintype "passive"))
      (node (ref "UC_SENZORI") (pin "17") (pinfunction "GP13_17") (pintype "bidirectional"))
    )
    (net (code "98") (name "/GP13_2") (class "Default")
      (node (ref "JS4") (pin "17") (pinfunction "17_17") (pintype "passive"))
      (node (ref "JS5") (pin "34") (pinfunction "34_34") (pintype "passive"))
      (node (ref "UC_EXTRA") (pin "17") (pinfunction "GP13_17") (pintype "bidirectional"))
    )
    (net (code "99") (name "/GP13_2_OUT") (class "Default")
      (node (ref "JS5") (pin "33") (pinfunction "33_33") (pintype "passive"))
      (node (ref "JS6") (pin "33") (pinfunction "33_33") (pintype "passive"))
      (node (ref "JS6") (pin "34") (pinfunction "34_34") (pintype "passive"))
    )
    (net (code "100") (name "/GP14") (class "Default")
      (node (ref "JS1") (pin "19") (pinfunction "19_19") (pintype "passive"))
      (node (ref "JS2") (pin "38") (pinfunction "38_38") (pintype "passive"))
      (node (ref "UC_SENZORI") (pin "19") (pinfunction "GP14_19") (pintype "bidirectional"))
    )
    (net (code "101") (name "/GP14_2") (class "Default")
      (node (ref "JS4") (pin "19") (pinfunction "19_19") (pintype "passive"))
      (node (ref "JS5") (pin "38") (pinfunction "38_38") (pintype "passive"))
      (node (ref "UC_EXTRA") (pin "19") (pinfunction "GP14_19") (pintype "bidirectional"))
    )
    (net (code "102") (name "/GP14_2_OUT") (class "Default")
      (node (ref "JS5") (pin "37") (pinfunction "37_37") (pintype "passive"))
      (node (ref "JS6") (pin "37") (pinfunction "37_37") (pintype "passive"))
      (node (ref "JS6") (pin "38") (pinfunction "38_38") (pintype "passive"))
    )
    (net (code "103") (name "/GP15") (class "Default")
      (node (ref "JS1") (pin "20") (pinfunction "20_20") (pintype "passive"))
      (node (ref "JS2") (pin "40") (pinfunction "40_40") (pintype "passive"))
      (node (ref "UC_SENZORI") (pin "20") (pinfunction "GP15_20") (pintype "bidirectional"))
    )
    (net (code "104") (name "/GP15_2") (class "Default")
      (node (ref "JS4") (pin "20") (pinfunction "20_20") (pintype "passive"))
      (node (ref "JS5") (pin "40") (pinfunction "40_40") (pintype "passive"))
      (node (ref "UC_EXTRA") (pin "20") (pinfunction "GP15_20") (pintype "bidirectional"))
    )
    (net (code "105") (name "/GP15_2_OUT") (class "Default")
      (node (ref "JS5") (pin "39") (pinfunction "39_39") (pintype "passive"))
      (node (ref "JS6") (pin "39") (pinfunction "39_39") (pintype "passive"))
      (node (ref "JS6") (pin "40") (pinfunction "40_40") (pintype "passive"))
    )
    (net (code "106") (name "/GP16") (class "Default")
      (node (ref "JD1") (pin "20") (pinfunction "20_20") (pintype "passive"))
      (node (ref "JD2") (pin "39") (pinfunction "39_39") (pintype "passive"))
      (node (ref "UC_SENZORI") (pin "21") (pinfunction "GP16_21") (pintype "bidirectional"))
    )
    (net (code "107") (name "/GP16_2") (class "Default")
      (node (ref "JD4") (pin "20") (pinfunction "20_20") (pintype "passive"))
      (node (ref "JD5") (pin "39") (pinfunction "39_39") (pintype "passive"))
      (node (ref "UC_EXTRA") (pin "21") (pinfunction "GP16_21") (pintype "bidirectional"))
    )
    (net (code "108") (name "/GP17") (class "Default")
      (node (ref "JD1") (pin "19") (pinfunction "19_19") (pintype "passive"))
      (node (ref "JD2") (pin "37") (pinfunction "37_37") (pintype "passive"))
      (node (ref "UC_SENZORI") (pin "22") (pinfunction "GP17_22") (pintype "bidirectional"))
    )
    (net (code "109") (name "/GP17_2") (class "Default")
      (node (ref "JD4") (pin "19") (pinfunction "19_19") (pintype "passive"))
      (node (ref "JD5") (pin "37") (pinfunction "37_37") (pintype "passive"))
      (node (ref "UC_EXTRA") (pin "22") (pinfunction "GP17_22") (pintype "bidirectional"))
    )
    (net (code "110") (name "/GP18") (class "Default")
      (node (ref "JD1") (pin "17") (pinfunction "17_17") (pintype "passive"))
      (node (ref "JD2") (pin "33") (pinfunction "33_33") (pintype "passive"))
      (node (ref "UC_SENZORI") (pin "24") (pinfunction "GP18_24") (pintype "bidirectional"))
    )
    (net (code "111") (name "/GP18_2") (class "Default")
      (node (ref "JD4") (pin "17") (pinfunction "17_17") (pintype "passive"))
      (node (ref "JD5") (pin "33") (pinfunction "33_33") (pintype "passive"))
      (node (ref "UC_EXTRA") (pin "24") (pinfunction "GP18_24") (pintype "bidirectional"))
    )
    (net (code "112") (name "/GP18_2_OUT") (class "Default")
      (node (ref "JD5") (pin "34") (pinfunction "34_34") (pintype "passive"))
      (node (ref "JD6") (pin "33") (pinfunction "33_33") (pintype "passive"))
      (node (ref "JD6") (pin "34") (pinfunction "34_34") (pintype "passive"))
    )
    (net (code "113") (name "/GP19") (class "Default")
      (node (ref "JD1") (pin "16") (pinfunction "16_16") (pintype "passive"))
      (node (ref "JD2") (pin "31") (pinfunction "31_31") (pintype "passive"))
      (node (ref "UC_SENZORI") (pin "25") (pinfunction "GP19_25") (pintype "bidirectional"))
    )
    (net (code "114") (name "/GP19_2") (class "Default")
      (node (ref "JD4") (pin "16") (pinfunction "16_16") (pintype "passive"))
      (node (ref "JD5") (pin "31") (pinfunction "31_31") (pintype "passive"))
      (node (ref "UC_EXTRA") (pin "25") (pinfunction "GP19_25") (pintype "bidirectional"))
    )
    (net (code "115") (name "/GP19_2_OUT") (class "Default")
      (node (ref "JD5") (pin "32") (pinfunction "32_32") (pintype "passive"))
      (node (ref "JD6") (pin "31") (pinfunction "31_31") (pintype "passive"))
      (node (ref "JD6") (pin "32") (pinfunction "32_32") (pintype "passive"))
    )
    (net (code "116") (name "/GP20") (class "Default")
      (node (ref "JD1") (pin "15") (pinfunction "15_15") (pintype "passive"))
      (node (ref "JD2") (pin "29") (pinfunction "29_29") (pintype "passive"))
      (node (ref "UC_SENZORI") (pin "26") (pinfunction "GP20_26") (pintype "bidirectional"))
    )
    (net (code "117") (name "/GP20_2") (class "Default")
      (node (ref "JD4") (pin "15") (pinfunction "15_15") (pintype "passive"))
      (node (ref "JD5") (pin "29") (pinfunction "29_29") (pintype "passive"))
      (node (ref "UC_EXTRA") (pin "26") (pinfunction "GP20_26") (pintype "bidirectional"))
    )
    (net (code "118") (name "/GP20_2_OUT") (class "Default")
      (node (ref "JD5") (pin "30") (pinfunction "30_30") (pintype "passive"))
      (node (ref "JD6") (pin "29") (pinfunction "29_29") (pintype "passive"))
      (node (ref "JD6") (pin "30") (pinfunction "30_30") (pintype "passive"))
    )
    (net (code "119") (name "/GP21") (class "Default")
      (node (ref "JD1") (pin "14") (pinfunction "14_14") (pintype "passive"))
      (node (ref "JD2") (pin "27") (pinfunction "27_27") (pintype "passive"))
      (node (ref "UC_SENZORI") (pin "27") (pinfunction "GP21_27") (pintype "bidirectional"))
    )
    (net (code "120") (name "/GP21_2") (class "Default")
      (node (ref "JD4") (pin "14") (pinfunction "14_14") (pintype "passive"))
      (node (ref "JD5") (pin "27") (pinfunction "27_27") (pintype "passive"))
      (node (ref "UC_EXTRA") (pin "27") (pinfunction "GP21_27") (pintype "bidirectional"))
    )
    (net (code "121") (name "/GP21_2_OUT") (class "Default")
      (node (ref "JD5") (pin "28") (pinfunction "28_28") (pintype "passive"))
      (node (ref "JD6") (pin "27") (pinfunction "27_27") (pintype "passive"))
      (node (ref "JD6") (pin "28") (pinfunction "28_28") (pintype "passive"))
    )
    (net (code "122") (name "/GP22") (class "Default")
      (node (ref "JD1") (pin "12") (pinfunction "12_12") (pintype "passive"))
      (node (ref "JD2") (pin "23") (pinfunction "23_23") (pintype "passive"))
      (node (ref "UC_SENZORI") (pin "29") (pinfunction "GP22_29") (pintype "bidirectional"))
    )
    (net (code "123") (name "/GP22_2") (class "Default")
      (node (ref "JD4") (pin "12") (pinfunction "12_12") (pintype "passive"))
      (node (ref "JD5") (pin "23") (pinfunction "23_23") (pintype "passive"))
      (node (ref "UC_EXTRA") (pin "29") (pinfunction "GP22_29") (pintype "bidirectional"))
    )
    (net (code "124") (name "/GP22_2_OUT") (class "Default")
      (node (ref "JD5") (pin "24") (pinfunction "24_24") (pintype "passive"))
      (node (ref "JD6") (pin "23") (pinfunction "23_23") (pintype "passive"))
      (node (ref "JD6") (pin "24") (pinfunction "24_24") (pintype "passive"))
    )
    (net (code "125") (name "/GP22_OUT") (class "Default")
      (node (ref "JD2") (pin "24") (pinfunction "24_24") (pintype "passive"))
      (node (ref "JD3") (pin "12") (pinfunction "12_12") (pintype "passive"))
    )
    (net (code "126") (name "/GP26") (class "Default")
      (node (ref "JD1") (pin "10") (pinfunction "10_10") (pintype "passive"))
      (node (ref "JD2") (pin "19") (pinfunction "19_19") (pintype "passive"))
      (node (ref "UC_SENZORI") (pin "31") (pinfunction "GP26_31") (pintype "bidirectional"))
    )
    (net (code "127") (name "/GP26_2") (class "Default")
      (node (ref "JD4") (pin "10") (pinfunction "10_10") (pintype "passive"))
      (node (ref "JD5") (pin "19") (pinfunction "19_19") (pintype "passive"))
      (node (ref "UC_EXTRA") (pin "31") (pinfunction "GP26_31") (pintype "bidirectional"))
    )
    (net (code "128") (name "/GP26_2_OUT") (class "Default")
      (node (ref "JD5") (pin "20") (pinfunction "20_20") (pintype "passive"))
      (node (ref "JD6") (pin "19") (pinfunction "19_19") (pintype "passive"))
      (node (ref "JD6") (pin "20") (pinfunction "20_20") (pintype "passive"))
    )
    (net (code "129") (name "/GP27") (class "Default")
      (node (ref "JD1") (pin "9") (pinfunction "9_9") (pintype "passive"))
      (node (ref "JD2") (pin "17") (pinfunction "17_17") (pintype "passive"))
      (node (ref "UC_SENZORI") (pin "32") (pinfunction "GP27_32") (pintype "bidirectional"))
    )
    (net (code "130") (name "/GP27_2") (class "Default")
      (node (ref "JD4") (pin "9") (pinfunction "9_9") (pintype "passive"))
      (node (ref "JD5") (pin "17") (pinfunction "17_17") (pintype "passive"))
      (node (ref "UC_EXTRA") (pin "32") (pinfunction "GP27_32") (pintype "bidirectional"))
    )
    (net (code "131") (name "/GP27_2_OUT") (class "Default")
      (node (ref "JD5") (pin "18") (pinfunction "18_18") (pintype "passive"))
      (node (ref "JD6") (pin "17") (pinfunction "17_17") (pintype "passive"))
      (node (ref "JD6") (pin "18") (pinfunction "18_18") (pintype "passive"))
    )
    (net (code "132") (name "/GP28") (class "Default")
      (node (ref "JD1") (pin "7") (pinfunction "7_7") (pintype "passive"))
      (node (ref "JD2") (pin "13") (pinfunction "13_13") (pintype "passive"))
      (node (ref "UC_SENZORI") (pin "34") (pinfunction "GP28_34") (pintype "bidirectional"))
    )
    (net (code "133") (name "/GP28_2") (class "Default")
      (node (ref "JD4") (pin "7") (pinfunction "7_7") (pintype "passive"))
      (node (ref "JD5") (pin "13") (pinfunction "13_13") (pintype "passive"))
      (node (ref "UC_EXTRA") (pin "34") (pinfunction "GP28_34") (pintype "bidirectional"))
    )
    (net (code "134") (name "/GP28_2_OUT") (class "Default")
      (node (ref "JD5") (pin "14") (pinfunction "14_14") (pintype "passive"))
      (node (ref "JD6") (pin "13") (pinfunction "13_13") (pintype "passive"))
      (node (ref "JD6") (pin "14") (pinfunction "14_14") (pintype "passive"))
    )
    (net (code "135") (name "/INT_TSL") (class "Default")
      (node (ref "TSL2561") (pin "1") (pinfunction "1_1") (pintype "passive"))
      (node (ref "TSL2561") (pin "2") (pinfunction "2_2") (pintype "passive"))
    )
    (net (code "136") (name "/MQ1_DRAIN") (class "Default")
      (node (ref "MQ1") (pin "3") (pinfunction "3_3") (pintype "passive"))
      (node (ref "MQ1") (pin "4") (pinfunction "4_4") (pintype "passive"))
      (node (ref "U$1") (pin "3") (pinfunction "D_3") (pintype "bidirectional"))
    )
    (net (code "137") (name "/MQ2_DRAIN") (class "Default")
      (node (ref "MQ2") (pin "3") (pinfunction "3_3") (pintype "passive"))
      (node (ref "MQ2") (pin "4") (pinfunction "4_4") (pintype "passive"))
      (node (ref "U$7") (pin "3") (pinfunction "D_3") (pintype "bidirectional"))
    )
    (net (code "138") (name "/MQ3_DRAIN") (class "Default")
      (node (ref "MQ3") (pin "3") (pinfunction "3_3") (pintype "passive"))
      (node (ref "MQ3") (pin "4") (pinfunction "4_4") (pintype "passive"))
      (node (ref "U$8") (pin "3") (pinfunction "D_3") (pintype "bidirectional"))
    )
    (net (code "139") (name "/MQ4_DRAIN") (class "Default")
      (node (ref "MQ4") (pin "3") (pinfunction "3_3") (pintype "passive"))
      (node (ref "MQ4") (pin "4") (pinfunction "4_4") (pintype "passive"))
      (node (ref "U$9") (pin "3") (pinfunction "D_3") (pintype "bidirectional"))
    )
    (net (code "140") (name "/MQ5_DRAIN") (class "Default")
      (node (ref "MQ5") (pin "3") (pinfunction "3_3") (pintype "passive"))
      (node (ref "MQ5") (pin "4") (pinfunction "4_4") (pintype "passive"))
      (node (ref "U$10") (pin "3") (pinfunction "D_3") (pintype "bidirectional"))
    )
    (net (code "141") (name "/MQ6_DRAIN") (class "Default")
      (node (ref "MQ6") (pin "3") (pinfunction "3_3") (pintype "passive"))
      (node (ref "MQ6") (pin "4") (pinfunction "4_4") (pintype "passive"))
      (node (ref "U$11") (pin "3") (pinfunction "D_3") (pintype "bidirectional"))
    )
    (net (code "142") (name "/OUT_DHT") (class "Default")
      (node (ref "DHT22") (pin "2") (pinfunction "2_2") (pintype "passive"))
      (node (ref "JS2") (pin "3") (pinfunction "3_3") (pintype "passive"))
      (node (ref "JS3") (pin "2") (pinfunction "2_2") (pintype "passive"))
    )
    (net (code "143") (name "/RUN") (class "Default")
      (node (ref "JD1") (pin "11") (pinfunction "11_11") (pintype "passive"))
      (node (ref "JD2") (pin "21") (pinfunction "21_21") (pintype "passive"))
      (node (ref "UC_SENZORI") (pin "30") (pinfunction "~{RUN}_30") (pintype "input"))
    )
    (net (code "144") (name "/RUN_2") (class "Default")
      (node (ref "JD4") (pin "11") (pinfunction "11_11") (pintype "passive"))
      (node (ref "JD5") (pin "21") (pinfunction "21_21") (pintype "passive"))
      (node (ref "UC_EXTRA") (pin "30") (pinfunction "~{RUN}_30") (pintype "input"))
    )
    (net (code "145") (name "/RUN_IN") (class "Default")
      (node (ref "JD2") (pin "22") (pinfunction "22_22") (pintype "passive"))
      (node (ref "JD3") (pin "11") (pinfunction "11_11") (pintype "passive"))
    )
    (net (code "146") (name "/RUN_IN_2") (class "Default")
      (node (ref "JD5") (pin "22") (pinfunction "22_22") (pintype "passive"))
      (node (ref "JD6") (pin "21") (pinfunction "21_21") (pintype "passive"))
      (node (ref "JD6") (pin "22") (pinfunction "22_22") (pintype "passive"))
    )
    (net (code "147") (name "/S0_MUX") (class "Default")
      (node (ref "JD2") (pin "28") (pinfunction "28_28") (pintype "passive"))
      (node (ref "JD3") (pin "14") (pinfunction "14_14") (pintype "passive"))
      (node (ref "MUX") (pin "20") (pinfunction "S0_20") (pintype "bidirectional"))
    )
    (net (code "148") (name "/S1_MUX") (class "Default")
      (node (ref "JD2") (pin "30") (pinfunction "30_30") (pintype "passive"))
      (node (ref "JD3") (pin "15") (pinfunction "15_15") (pintype "passive"))
      (node (ref "MUX") (pin "21") (pinfunction "S1_21") (pintype "bidirectional"))
    )
    (net (code "149") (name "/S2_MUX") (class "Default")
      (node (ref "JD2") (pin "32") (pinfunction "32_32") (pintype "passive"))
      (node (ref "JD3") (pin "16") (pinfunction "16_16") (pintype "passive"))
      (node (ref "MUX") (pin "22") (pinfunction "S2_22") (pintype "bidirectional"))
    )
    (net (code "150") (name "/S3_MUX") (class "Default")
      (node (ref "JD2") (pin "34") (pinfunction "34_34") (pintype "passive"))
      (node (ref "JD3") (pin "17") (pinfunction "17_17") (pintype "passive"))
      (node (ref "MUX") (pin "23") (pinfunction "S3_23") (pintype "bidirectional"))
    )
    (net (code "151") (name "/SCL_BMP") (class "Default")
      (node (ref "BMP280") (pin "5") (pinfunction "5_5") (pintype "passive"))
      (node (ref "BMP280") (pin "6") (pinfunction "6_6") (pintype "passive"))
      (node (ref "JS2") (pin "23") (pinfunction "23_23") (pintype "passive"))
      (node (ref "JS3") (pin "12") (pinfunction "12_12") (pintype "passive"))
    )
    (net (code "152") (name "/SCL_TSL") (class "Default")
      (node (ref "JS2") (pin "9") (pinfunction "9_9") (pintype "passive"))
      (node (ref "JS3") (pin "5") (pinfunction "5_5") (pintype "passive"))
      (node (ref "TSL2561") (pin "5") (pinfunction "5_5") (pintype "passive"))
      (node (ref "TSL2561") (pin "6") (pinfunction "6_6") (pintype "passive"))
    )
    (net (code "153") (name "/SDA_BMP") (class "Default")
      (node (ref "BMP280") (pin "7") (pinfunction "7_7") (pintype "passive"))
      (node (ref "BMP280") (pin "8") (pinfunction "8_8") (pintype "passive"))
      (node (ref "JS2") (pin "21") (pinfunction "21_21") (pintype "passive"))
      (node (ref "JS3") (pin "11") (pinfunction "11_11") (pintype "passive"))
    )
    (net (code "154") (name "/SDA_TSL") (class "Default")
      (node (ref "JS2") (pin "7") (pinfunction "7_7") (pintype "passive"))
      (node (ref "JS3") (pin "4") (pinfunction "4_4") (pintype "passive"))
      (node (ref "TSL2561") (pin "3") (pinfunction "3_3") (pintype "passive"))
      (node (ref "TSL2561") (pin "4") (pinfunction "4_4") (pintype "passive"))
    )
    (net (code "155") (name "/SDO_BMP") (class "Default")
      (node (ref "BMP280") (pin "11") (pinfunction "11_11") (pintype "passive"))
      (node (ref "BMP280") (pin "12") (pinfunction "12_12") (pintype "passive"))
    )
    (net (code "156") (name "/SIG_ADC") (class "Default")
      (node (ref "JD2") (pin "18") (pinfunction "18_18") (pintype "passive"))
      (node (ref "JD2") (pin "20") (pinfunction "20_20") (pintype "passive"))
      (node (ref "JD3") (pin "10") (pinfunction "10_10") (pintype "passive"))
      (node (ref "JD3") (pin "9") (pinfunction "9_9") (pintype "passive"))
      (node (ref "MUX") (pin "24") (pinfunction "SIG_24") (pintype "bidirectional"))
    )
    (net (code "157") (name "/SWCLK") (class "Default")
      (node (ref "UC_SENZORI") (pin "D1") (pinfunction "SWCLK_D1") (pintype "input"))
    )
    (net (code "158") (name "/SWCLK_2") (class "Default")
      (node (ref "UC_EXTRA") (pin "D1") (pinfunction "SWCLK_D1") (pintype "input"))
    )
    (net (code "159") (name "/SWDIO") (class "Default")
      (node (ref "UC_SENZORI") (pin "D3") (pinfunction "SWDIO_D3") (pintype "bidirectional"))
    )
    (net (code "160") (name "/SWDIO_2") (class "Default")
      (node (ref "UC_EXTRA") (pin "D3") (pinfunction "SWDIO_D3") (pintype "bidirectional"))
    )
    (net (code "161") (name "/TP1") (class "Default")
      (node (ref "UC_SENZORI") (pin "TP1") (pinfunction "TP1_GND_TP1") (pintype "power_in"))
    )
    (net (code "162") (name "/TP1_2") (class "Default")
      (node (ref "UC_EXTRA") (pin "TP1") (pinfunction "TP1_GND_TP1") (pintype "power_in"))
    )
    (net (code "163") (name "/TP2") (class "Default")
      (node (ref "UC_SENZORI") (pin "TP2") (pinfunction "TP2_USB_DM_TP2") (pintype "bidirectional"))
    )
    (net (code "164") (name "/TP2_2") (class "Default")
      (node (ref "UC_EXTRA") (pin "TP2") (pinfunction "TP2_USB_DM_TP2") (pintype "bidirectional"))
    )
    (net (code "165") (name "/TP3") (class "Default")
      (node (ref "UC_SENZORI") (pin "TP3") (pinfunction "TP3_USB_DP_TP3") (pintype "bidirectional"))
    )
    (net (code "166") (name "/TP3_2") (class "Default")
      (node (ref "UC_EXTRA") (pin "TP3") (pinfunction "TP3_USB_DP_TP3") (pintype "bidirectional"))
    )
    (net (code "167") (name "/TP5") (class "Default")
      (node (ref "UC_SENZORI") (pin "TP5") (pinfunction "TP5_GPIO25/LED_TP5") (pintype "output"))
    )
    (net (code "168") (name "/TP5_2") (class "Default")
      (node (ref "UC_EXTRA") (pin "TP5") (pinfunction "TP5_GPIO25/LED_TP5") (pintype "output"))
    )
    (net (code "169") (name "/TP6") (class "Default")
      (node (ref "UC_SENZORI") (pin "TP6") (pinfunction "TP6_BOOTSEL_TP6") (pintype "input"))
    )
    (net (code "170") (name "/TP6_2") (class "Default")
      (node (ref "UC_EXTRA") (pin "TP6") (pinfunction "TP6_BOOTSEL_TP6") (pintype "input"))
    )
    (net (code "171") (name "/UART0_RX") (class "Default")
      (node (ref "JD2") (pin "38") (pinfunction "38_38") (pintype "passive"))
      (node (ref "JD3") (pin "19") (pinfunction "19_19") (pintype "passive"))
    )
    (net (code "172") (name "/UART0_RX_2") (class "Default")
      (node (ref "JD5") (pin "38") (pinfunction "38_38") (pintype "passive"))
      (node (ref "JD6") (pin "37") (pinfunction "37_37") (pintype "passive"))
      (node (ref "JD6") (pin "38") (pinfunction "38_38") (pintype "passive"))
    )
    (net (code "173") (name "/UART0_TX") (class "Default")
      (node (ref "JD2") (pin "40") (pinfunction "40_40") (pintype "passive"))
      (node (ref "JD3") (pin "20") (pinfunction "20_20") (pintype "passive"))
    )
    (net (code "174") (name "/UART0_TX_2") (class "Default")
      (node (ref "JD5") (pin "40") (pinfunction "40_40") (pintype "passive"))
      (node (ref "JD6") (pin "39") (pinfunction "39_39") (pintype "passive"))
      (node (ref "JD6") (pin "40") (pinfunction "40_40") (pintype "passive"))
    )
    (net (code "175") (name "/VBUS") (class "Default")
      (node (ref "JD1") (pin "1") (pinfunction "1_1") (pintype "passive"))
      (node (ref "JD2") (pin "1") (pinfunction "1_1") (pintype "passive"))
      (node (ref "UC_SENZORI") (pin "40") (pinfunction "VBUS_40") (pintype "power_in"))
    )
    (net (code "176") (name "/VBUS_2") (class "Default")
      (node (ref "JD4") (pin "1") (pinfunction "1_1") (pintype "passive"))
      (node (ref "JD5") (pin "1") (pinfunction "1_1") (pintype "passive"))
      (node (ref "UC_EXTRA") (pin "40") (pinfunction "VBUS_40") (pintype "power_in"))
    )
    (net (code "177") (name "/VBUS_2_OUT") (class "Default")
      (node (ref "JD5") (pin "2") (pinfunction "2_2") (pintype "passive"))
      (node (ref "JD6") (pin "1") (pinfunction "1_1") (pintype "passive"))
      (node (ref "JD6") (pin "2") (pinfunction "2_2") (pintype "passive"))
    )
    (net (code "178") (name "/VBUS_OUT") (class "Default")
      (node (ref "JD2") (pin "2") (pinfunction "2_2") (pintype "passive"))
      (node (ref "JD3") (pin "1") (pinfunction "1_1") (pintype "passive"))
    )
    (net (code "179") (name "/VSYS") (class "Default")
      (node (ref "JD1") (pin "2") (pinfunction "2_2") (pintype "passive"))
      (node (ref "JD2") (pin "3") (pinfunction "3_3") (pintype "passive"))
      (node (ref "UC_SENZORI") (pin "39") (pinfunction "VSYS_39") (pintype "power_in"))
    )
    (net (code "180") (name "/VSYS_2") (class "Default")
      (node (ref "JD4") (pin "2") (pinfunction "2_2") (pintype "passive"))
      (node (ref "JD5") (pin "3") (pinfunction "3_3") (pintype "passive"))
      (node (ref "UC_EXTRA") (pin "39") (pinfunction "VSYS_39") (pintype "power_in"))
    )
    (net (code "181") (name "GND") (class "Default")
      (node (ref "BATT_11_1") (pin "N") (pinfunction "NEG_N") (pintype "passive"))
      (node (ref "BMP280") (pin "3") (pinfunction "3_3") (pintype "passive"))
      (node (ref "BMP280") (pin "4") (pinfunction "4_4") (pintype "passive"))
      (node (ref "DHT22") (pin "3") (pinfunction "3_3") (pintype "passive"))
      (node (ref "JD1") (pin "13") (pinfunction "13_13") (pintype "passive"))
      (node (ref "JD1") (pin "18") (pinfunction "18_18") (pintype "passive"))
      (node (ref "JD1") (pin "3") (pinfunction "3_3") (pintype "passive"))
      (node (ref "JD2") (pin "16") (pinfunction "16_16") (pintype "passive"))
      (node (ref "JD2") (pin "25") (pinfunction "25_25") (pintype "passive"))
      (node (ref "JD2") (pin "26") (pinfunction "26_26") (pintype "passive"))
      (node (ref "JD2") (pin "35") (pinfunction "35_35") (pintype "passive"))
      (node (ref "JD2") (pin "36") (pinfunction "36_36") (pintype "passive"))
      (node (ref "JD2") (pin "5") (pinfunction "5_5") (pintype "passive"))
      (node (ref "JD2") (pin "6") (pinfunction "6_6") (pintype "passive"))
      (node (ref "JD3") (pin "13") (pinfunction "13_13") (pintype "passive"))
      (node (ref "JD3") (pin "18") (pinfunction "18_18") (pintype "passive"))
      (node (ref "JD3") (pin "3") (pinfunction "3_3") (pintype "passive"))
      (node (ref "JD3") (pin "8") (pinfunction "8_8") (pintype "passive"))
      (node (ref "JD4") (pin "13") (pinfunction "13_13") (pintype "passive"))
      (node (ref "JD4") (pin "18") (pinfunction "18_18") (pintype "passive"))
      (node (ref "JD4") (pin "3") (pinfunction "3_3") (pintype "passive"))
      (node (ref "JD5") (pin "16") (pinfunction "16_16") (pintype "passive"))
      (node (ref "JD5") (pin "25") (pinfunction "25_25") (pintype "passive"))
      (node (ref "JD5") (pin "26") (pinfunction "26_26") (pintype "passive"))
      (node (ref "JD5") (pin "35") (pinfunction "35_35") (pintype "passive"))
      (node (ref "JD5") (pin "36") (pinfunction "36_36") (pintype "passive"))
      (node (ref "JD5") (pin "5") (pinfunction "5_5") (pintype "passive"))
      (node (ref "JD5") (pin "6") (pinfunction "6_6") (pintype "passive"))
      (node (ref "JD6") (pin "15") (pinfunction "15_15") (pintype "passive"))
      (node (ref "JD6") (pin "16") (pinfunction "16_16") (pintype "passive"))
      (node (ref "JD6") (pin "25") (pinfunction "25_25") (pintype "passive"))
      (node (ref "JD6") (pin "26") (pinfunction "26_26") (pintype "passive"))
      (node (ref "JD6") (pin "35") (pinfunction "35_35") (pintype "passive"))
      (node (ref "JD6") (pin "36") (pinfunction "36_36") (pintype "passive"))
      (node (ref "JD6") (pin "5") (pinfunction "5_5") (pintype "passive"))
      (node (ref "JD6") (pin "6") (pinfunction "6_6") (pintype "passive"))
      (node (ref "JS1") (pin "13") (pinfunction "13_13") (pintype "passive"))
      (node (ref "JS1") (pin "18") (pinfunction "18_18") (pintype "passive"))
      (node (ref "JS1") (pin "3") (pinfunction "3_3") (pintype "passive"))
      (node (ref "JS1") (pin "8") (pinfunction "8_8") (pintype "passive"))
      (node (ref "JS2") (pin "15") (pinfunction "15_15") (pintype "passive"))
      (node (ref "JS2") (pin "16") (pinfunction "16_16") (pintype "passive"))
      (node (ref "JS2") (pin "25") (pinfunction "25_25") (pintype "passive"))
      (node (ref "JS2") (pin "26") (pinfunction "26_26") (pintype "passive"))
      (node (ref "JS2") (pin "35") (pinfunction "35_35") (pintype "passive"))
      (node (ref "JS2") (pin "36") (pinfunction "36_36") (pintype "passive"))
      (node (ref "JS2") (pin "5") (pinfunction "5_5") (pintype "passive"))
      (node (ref "JS2") (pin "6") (pinfunction "6_6") (pintype "passive"))
      (node (ref "JS3") (pin "13") (pinfunction "13_13") (pintype "passive"))
      (node (ref "JS3") (pin "18") (pinfunction "18_18") (pintype "passive"))
      (node (ref "JS3") (pin "3") (pinfunction "3_3") (pintype "passive"))
      (node (ref "JS3") (pin "8") (pinfunction "8_8") (pintype "passive"))
      (node (ref "JS4") (pin "13") (pinfunction "13_13") (pintype "passive"))
      (node (ref "JS4") (pin "18") (pinfunction "18_18") (pintype "passive"))
      (node (ref "JS4") (pin "3") (pinfunction "3_3") (pintype "passive"))
      (node (ref "JS4") (pin "8") (pinfunction "8_8") (pintype "passive"))
      (node (ref "JS5") (pin "15") (pinfunction "15_15") (pintype "passive"))
      (node (ref "JS5") (pin "16") (pinfunction "16_16") (pintype "passive"))
      (node (ref "JS5") (pin "25") (pinfunction "25_25") (pintype "passive"))
      (node (ref "JS5") (pin "26") (pinfunction "26_26") (pintype "passive"))
      (node (ref "JS5") (pin "35") (pinfunction "35_35") (pintype "passive"))
      (node (ref "JS5") (pin "36") (pinfunction "36_36") (pintype "passive"))
      (node (ref "JS5") (pin "5") (pinfunction "5_5") (pintype "passive"))
      (node (ref "JS5") (pin "6") (pinfunction "6_6") (pintype "passive"))
      (node (ref "JS6") (pin "15") (pinfunction "15_15") (pintype "passive"))
      (node (ref "JS6") (pin "16") (pinfunction "16_16") (pintype "passive"))
      (node (ref "JS6") (pin "25") (pinfunction "25_25") (pintype "passive"))
      (node (ref "JS6") (pin "26") (pinfunction "26_26") (pintype "passive"))
      (node (ref "JS6") (pin "35") (pinfunction "35_35") (pintype "passive"))
      (node (ref "JS6") (pin "36") (pinfunction "36_36") (pintype "passive"))
      (node (ref "JS6") (pin "5") (pinfunction "5_5") (pintype "passive"))
      (node (ref "JS6") (pin "6") (pinfunction "6_6") (pintype "passive"))
      (node (ref "MUX") (pin "17") (pinfunction "GND_17") (pintype "bidirectional"))
      (node (ref "R10") (pin "1") (pinfunction "1_1") (pintype "passive"))
      (node (ref "R12") (pin "1") (pinfunction "1_1") (pintype "passive"))
      (node (ref "R2") (pin "1") (pinfunction "1_1") (pintype "passive"))
      (node (ref "R4") (pin "1") (pinfunction "1_1") (pintype "passive"))
      (node (ref "R6") (pin "1") (pinfunction "1_1") (pintype "passive"))
      (node (ref "R8") (pin "1") (pinfunction "1_1") (pintype "passive"))
      (node (ref "TSL2561") (pin "7") (pinfunction "7_7") (pintype "passive"))
      (node (ref "TSL2561") (pin "8") (pinfunction "8_8") (pintype "passive"))
      (node (ref "U$1") (pin "2") (pinfunction "S_2") (pintype "bidirectional"))
      (node (ref "U$10") (pin "2") (pinfunction "S_2") (pintype "bidirectional"))
      (node (ref "U$11") (pin "2") (pinfunction "S_2") (pintype "bidirectional"))
      (node (ref "U$2") (pin "11") (pinfunction "GND2_11") (pintype "bidirectional"))
      (node (ref "U$2") (pin "2") (pinfunction "GND1_2") (pintype "bidirectional"))
      (node (ref "U$3") (pin "11") (pinfunction "GND2_11") (pintype "bidirectional"))
      (node (ref "U$3") (pin "2") (pinfunction "GND1_2") (pintype "bidirectional"))
      (node (ref "U$4") (pin "11") (pinfunction "GND2_11") (pintype "bidirectional"))
      (node (ref "U$4") (pin "2") (pinfunction "GND1_2") (pintype "bidirectional"))
      (node (ref "U$5") (pin "3") (pinfunction "VI-_3") (pintype "input"))
      (node (ref "U$5") (pin "4") (pinfunction "VI-_4") (pintype "input"))
      (node (ref "U$5") (pin "7") (pinfunction "VO-_7") (pintype "output"))
      (node (ref "U$5") (pin "8") (pinfunction "VO-_8") (pintype "output"))
      (node (ref "U$7") (pin "2") (pinfunction "S_2") (pintype "bidirectional"))
      (node (ref "U$8") (pin "2") (pinfunction "S_2") (pintype "bidirectional"))
      (node (ref "U$9") (pin "2") (pinfunction "S_2") (pintype "bidirectional"))
      (node (ref "UC_EXTRA") (pin "13") (pinfunction "GND_13") (pintype "power_in"))
      (node (ref "UC_EXTRA") (pin "18") (pinfunction "GND_18") (pintype "power_in"))
      (node (ref "UC_EXTRA") (pin "23") (pinfunction "GND_23") (pintype "power_in"))
      (node (ref "UC_EXTRA") (pin "28") (pinfunction "GND_28") (pintype "power_in"))
      (node (ref "UC_EXTRA") (pin "3") (pinfunction "GND_3") (pintype "power_in"))
      (node (ref "UC_EXTRA") (pin "38") (pinfunction "GND_38") (pintype "power_in"))
      (node (ref "UC_EXTRA") (pin "8") (pinfunction "GND_8") (pintype "power_in"))
      (node (ref "UC_EXTRA") (pin "D2") (pinfunction "GND_D2") (pintype "power_in"))
      (node (ref "UC_SENZORI") (pin "13") (pinfunction "GND_13") (pintype "power_in"))
      (node (ref "UC_SENZORI") (pin "18") (pinfunction "GND_18") (pintype "power_in"))
      (node (ref "UC_SENZORI") (pin "23") (pinfunction "GND_23") (pintype "power_in"))
      (node (ref "UC_SENZORI") (pin "28") (pinfunction "GND_28") (pintype "power_in"))
      (node (ref "UC_SENZORI") (pin "3") (pinfunction "GND_3") (pintype "power_in"))
      (node (ref "UC_SENZORI") (pin "38") (pinfunction "GND_38") (pintype "power_in"))
      (node (ref "UC_SENZORI") (pin "8") (pinfunction "GND_8") (pintype "power_in"))
      (node (ref "UC_SENZORI") (pin "D2") (pinfunction "GND_D2") (pintype "power_in"))
    )
    (net (code "182") (name "Net-(U$1-G)") (class "Default")
      (node (ref "R1") (pin "1") (pinfunction "1_1") (pintype "passive"))
      (node (ref "U$1") (pin "1") (pinfunction "G_1") (pintype "bidirectional"))
    )
    (net (code "183") (name "Net-(U$7-G)") (class "Default")
      (node (ref "R3") (pin "1") (pinfunction "1_1") (pintype "passive"))
      (node (ref "U$7") (pin "1") (pinfunction "G_1") (pintype "bidirectional"))
    )
    (net (code "184") (name "Net-(U$8-G)") (class "Default")
      (node (ref "R5") (pin "1") (pinfunction "1_1") (pintype "passive"))
      (node (ref "U$8") (pin "1") (pinfunction "G_1") (pintype "bidirectional"))
    )
    (net (code "185") (name "Net-(U$9-G)") (class "Default")
      (node (ref "R7") (pin "1") (pinfunction "1_1") (pintype "passive"))
      (node (ref "U$9") (pin "1") (pinfunction "G_1") (pintype "bidirectional"))
    )
    (net (code "186") (name "Net-(U$10-G)") (class "Default")
      (node (ref "R9") (pin "1") (pinfunction "1_1") (pintype "passive"))
      (node (ref "U$10") (pin "1") (pinfunction "G_1") (pintype "bidirectional"))
    )
    (net (code "187") (name "Net-(U$11-G)") (class "Default")
      (node (ref "R11") (pin "1") (pinfunction "1_1") (pintype "passive"))
      (node (ref "U$11") (pin "1") (pinfunction "G_1") (pintype "bidirectional"))
    )
    (net (code "188") (name "unconnected-(UC_EXTRA-TP4_GPIO23{slash}SMPS_PS-PadTP4)") (class "Default")
      (node (ref "UC_EXTRA") (pin "TP4") (pinfunction "TP4_GPIO23/SMPS_PS_TP4") (pintype "no_connect"))
    )
    (net (code "189") (name "unconnected-(UC_SENZORI-TP4_GPIO23{slash}SMPS_PS-PadTP4)") (class "Default")
      (node (ref "UC_SENZORI") (pin "TP4") (pinfunction "TP4_GPIO23/SMPS_PS_TP4") (pintype "no_connect"))
    )
  )
)
